# astable.net
KiCad netlist of a schematic drawn in EAGLE
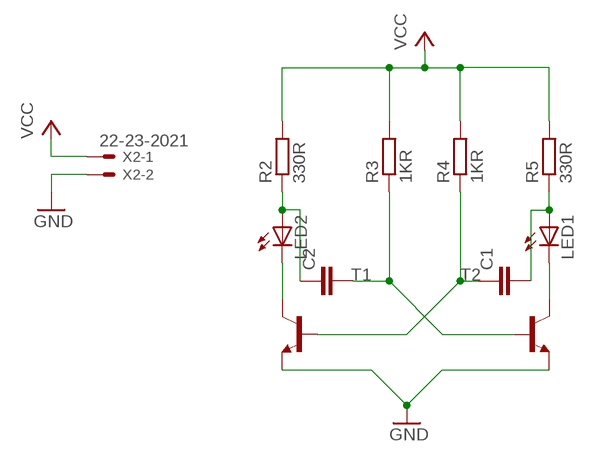
[diagram p0: schematic, sheet 1]

(export (version "E")
  (design (tool "Eeschema 10.0.6"))
  (components
    (comp (ref "C1")
      (value "C-EU025-030X050")
      (footprint "eagle-import:C025-030X050")
      (libsource (lib "eagle-import") (part "C-EU025-030X050"))
    )
    (comp (ref "C2")
      (value "C-EU025-030X050")
      (footprint "eagle-import:C025-030X050")
      (libsource (lib "eagle-import") (part "C-EU025-030X050"))
    )
    (comp (ref "LED1")
      (value "LED5MM")
      (footprint "eagle-import:LED5MM")
      (libsource (lib "eagle-import") (part "LED5MM"))
    )
    (comp (ref "LED2")
      (value "LED5MM")
      (footprint "eagle-import:LED5MM")
      (libsource (lib "eagle-import") (part "LED5MM"))
    )
    (comp (ref "R2")
      (value "330R")
      (footprint "eagle-import:0207_10")
      (libsource (lib "eagle-import") (part "R-EU_0207/10"))
    )
    (comp (ref "R3")
      (value "1KR")
      (footprint "eagle-import:0207_10")
      (libsource (lib "eagle-import") (part "R-EU_0207/10"))
    )
    (comp (ref "R4")
      (value "1KR")
      (footprint "eagle-import:0207_10")
      (libsource (lib "eagle-import") (part "R-EU_0207/10"))
    )
    (comp (ref "R5")
      (value "330R")
      (footprint "eagle-import:0207_10")
      (libsource (lib "eagle-import") (part "R-EU_0207/10"))
    )
    (comp (ref "T1")
      (value "-NPN-TO92-E1")
      (footprint "eagle-import:TO92-E1")
      (libsource (lib "eagle-import") (part "-NPN-TO92-E1"))
    )
    (comp (ref "T2")
      (value "-NPN-TO92-E1")
      (footprint "eagle-import:TO92-E1")
      (libsource (lib "eagle-import") (part "-NPN-TO92-E1"))
    )
    (comp (ref "X2")
      (value "22-23-2021")
      (footprint "eagle-import:22-23-2021")
      (fields (field (name "MF") "MOLEX"))
      (libsource (lib "eagle-import") (part "22-23-2021"))
    )
  )
  (nets
    (net (code "1") (name "GND") (class "Default")
      (node (ref "T1") (pin "3") (pinfunction "E_3") (pintype "passive"))
      (node (ref "T2") (pin "3") (pinfunction "E_3") (pintype "passive"))
      (node (ref "X2") (pin "2") (pinfunction "S_2") (pintype "passive"))
    )
    (net (code "2") (name "Net-(C1-Pad2)") (class "Default")
      (node (ref "C1") (pin "2") (pinfunction "2_2") (pintype "passive"))
      (node (ref "LED1") (pin "A") (pinfunction "A_A") (pintype "passive"))
      (node (ref "R5") (pin "1") (pinfunction "1_1") (pintype "passive"))
    )
    (net (code "3") (name "Net-(C2-Pad1)") (class "Default")
      (node (ref "C2") (pin "1") (pinfunction "1_1") (pintype "passive"))
      (node (ref "LED2") (pin "A") (pinfunction "A_A") (pintype "passive"))
      (node (ref "R2") (pin "1") (pinfunction "1_1") (pintype "passive"))
    )
    (net (code "4") (name "Net-(LED1-C)") (class "Default")
      (node (ref "LED1") (pin "K") (pinfunction "C_K") (pintype "passive"))
      (node (ref "T2") (pin "1") (pinfunction "C_1") (pintype "passive"))
    )
    (net (code "5") (name "Net-(LED2-C)") (class "Default")
      (node (ref "LED2") (pin "K") (pinfunction "C_K") (pintype "passive"))
      (node (ref "T1") (pin "1") (pinfunction "C_1") (pintype "passive"))
    )
    (net (code "6") (name "Net-(T1-B)") (class "Default")
      (node (ref "C1") (pin "1") (pinfunction "1_1") (pintype "passive"))
      (node (ref "R4") (pin "1") (pinfunction "1_1") (pintype "passive"))
      (node (ref "T1") (pin "2") (pinfunction "B_2") (pintype "passive"))
    )
    (net (code "7") (name "Net-(T2-B)") (class "Default")
      (node (ref "C2") (pin "2") (pinfunction "2_2") (pintype "passive"))
      (node (ref "R3") (pin "1") (pinfunction "1_1") (pintype "passive"))
      (node (ref "T2") (pin "2") (pinfunction "B_2") (pintype "passive"))
    )
    (net (code "8") (name "VCC") (class "Default")
      (node (ref "R2") (pin "2") (pinfunction "2_2") (pintype "passive"))
      (node (ref "R3") (pin "2") (pinfunction "2_2") (pintype "passive"))
      (node (ref "R4") (pin "2") (pinfunction "2_2") (pintype "passive"))
      (node (ref "R5") (pin "2") (pinfunction "2_2") (pintype "passive"))
      (node (ref "X2") (pin "1") (pinfunction "S_1") (pintype "passive"))
    )
  )
)
